# USBready.net
KiCad netlist of a schematic drawn in EAGLE
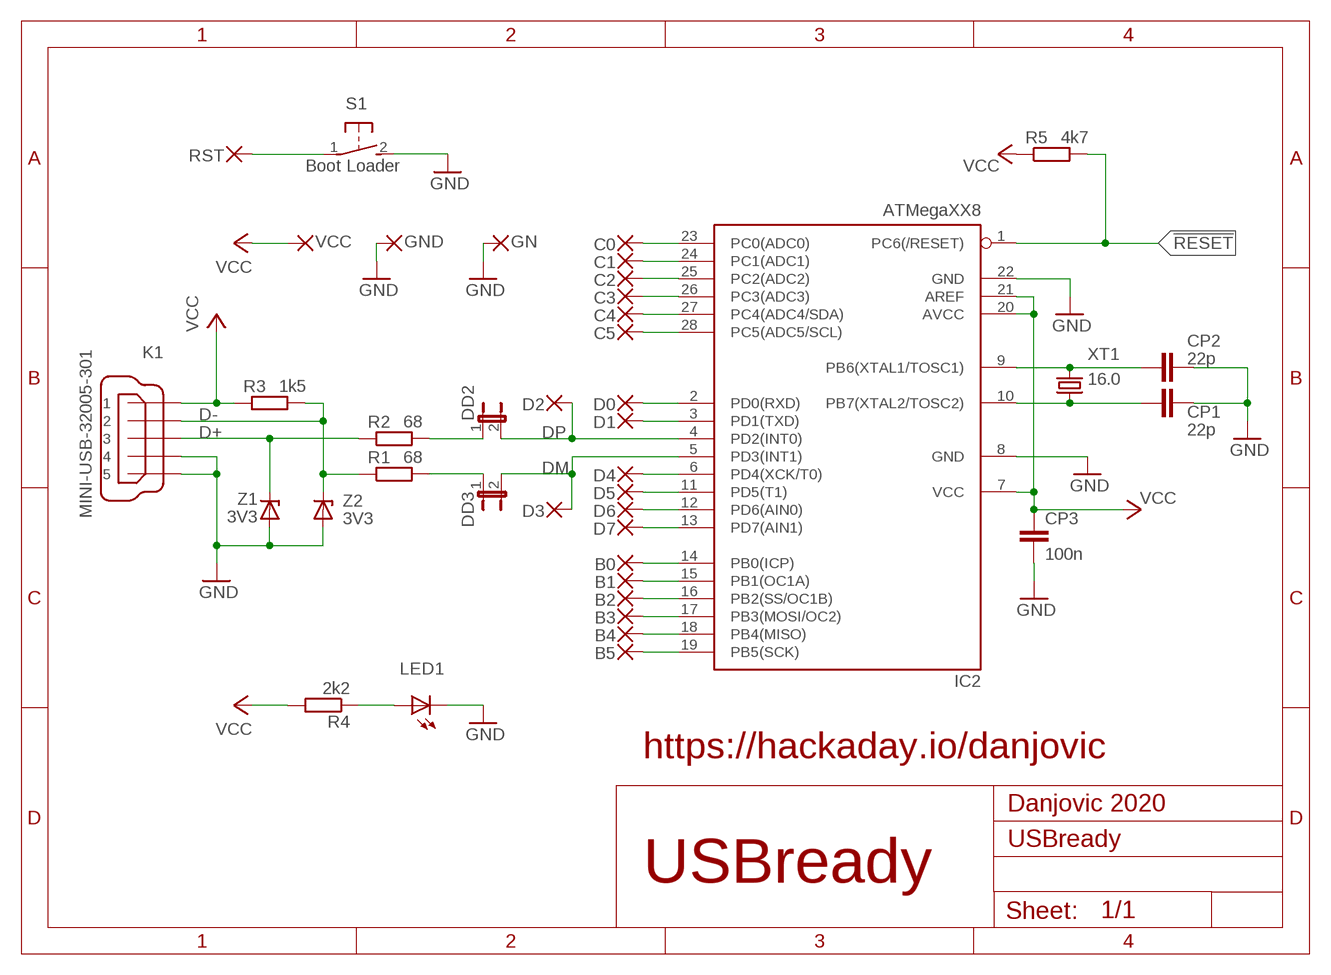
[diagram p0: schematic, sheet 1]

(export (version "E")
  (design (tool "Eeschema 10.0.6"))
  (components
    (comp (ref "B0")
      (value "WIREPAD1,6/0,9")
      (footprint "eagle-import:1,6_0,9")
      (libsource (lib "eagle-import") (part "WIREPAD1,6/0,9"))
    )
    (comp (ref "B1")
      (value "WIREPAD1,6/0,9")
      (footprint "eagle-import:1,6_0,9")
      (libsource (lib "eagle-import") (part "WIREPAD1,6/0,9"))
    )
    (comp (ref "B2")
      (value "WIREPAD1,6/0,9")
      (footprint "eagle-import:1,6_0,9")
      (libsource (lib "eagle-import") (part "WIREPAD1,6/0,9"))
    )
    (comp (ref "B3")
      (value "WIREPAD1,6/0,9")
      (footprint "eagle-import:1,6_0,9")
      (libsource (lib "eagle-import") (part "WIREPAD1,6/0,9"))
    )
    (comp (ref "B4")
      (value "WIREPAD1,6/0,9")
      (footprint "eagle-import:1,6_0,9")
      (libsource (lib "eagle-import") (part "WIREPAD1,6/0,9"))
    )
    (comp (ref "B5")
      (value "WIREPAD1,6/0,9")
      (footprint "eagle-import:1,6_0,9")
      (libsource (lib "eagle-import") (part "WIREPAD1,6/0,9"))
    )
    (comp (ref "C0")
      (value "WIREPAD1,6/0,9")
      (footprint "eagle-import:1,6_0,9")
      (libsource (lib "eagle-import") (part "WIREPAD1,6/0,9"))
    )
    (comp (ref "C1")
      (value "WIREPAD1,6/0,9")
      (footprint "eagle-import:1,6_0,9")
      (libsource (lib "eagle-import") (part "WIREPAD1,6/0,9"))
    )
    (comp (ref "C2")
      (value "WIREPAD1,6/0,9")
      (footprint "eagle-import:1,6_0,9")
      (libsource (lib "eagle-import") (part "WIREPAD1,6/0,9"))
    )
    (comp (ref "C3")
      (value "WIREPAD1,6/0,9")
      (footprint "eagle-import:1,6_0,9")
      (libsource (lib "eagle-import") (part "WIREPAD1,6/0,9"))
    )
    (comp (ref "C4")
      (value "WIREPAD1,6/0,9")
      (footprint "eagle-import:1,6_0,9")
      (libsource (lib "eagle-import") (part "WIREPAD1,6/0,9"))
    )
    (comp (ref "C5")
      (value "WIREPAD1,6/0,9")
      (footprint "eagle-import:1,6_0,9")
      (libsource (lib "eagle-import") (part "WIREPAD1,6/0,9"))
    )
    (comp (ref "CP1")
      (value "22p")
      (footprint "eagle-import:C0805")
      (libsource (lib "eagle-import") (part "C-EUC0805"))
    )
    (comp (ref "CP2")
      (value "22p")
      (footprint "eagle-import:C0805")
      (libsource (lib "eagle-import") (part "C-EUC0805"))
    )
    (comp (ref "CP3")
      (value "100n")
      (footprint "eagle-import:C0805")
      (libsource (lib "eagle-import") (part "C-EUC0805"))
    )
    (comp (ref "D0")
      (value "WIREPAD1,6/0,9")
      (footprint "eagle-import:1,6_0,9")
      (libsource (lib "eagle-import") (part "WIREPAD1,6/0,9"))
    )
    (comp (ref "D1")
      (value "WIREPAD1,6/0,9")
      (footprint "eagle-import:1,6_0,9")
      (libsource (lib "eagle-import") (part "WIREPAD1,6/0,9"))
    )
    (comp (ref "D2")
      (value "WIREPAD1,6/0,9")
      (footprint "eagle-import:1,6_0,9")
      (libsource (lib "eagle-import") (part "WIREPAD1,6/0,9"))
    )
    (comp (ref "D3")
      (value "WIREPAD1,6/0,9")
      (footprint "eagle-import:1,6_0,9")
      (libsource (lib "eagle-import") (part "WIREPAD1,6/0,9"))
    )
    (comp (ref "D4")
      (value "WIREPAD1,6/0,9")
      (footprint "eagle-import:1,6_0,9")
      (libsource (lib "eagle-import") (part "WIREPAD1,6/0,9"))
    )
    (comp (ref "D5")
      (value "WIREPAD1,6/0,9")
      (footprint "eagle-import:1,6_0,9")
      (libsource (lib "eagle-import") (part "WIREPAD1,6/0,9"))
    )
    (comp (ref "D6")
      (value "WIREPAD1,6/0,9")
      (footprint "eagle-import:1,6_0,9")
      (libsource (lib "eagle-import") (part "WIREPAD1,6/0,9"))
    )
    (comp (ref "D7")
      (value "WIREPAD1,6/0,9")
      (footprint "eagle-import:1,6_0,9")
      (libsource (lib "eagle-import") (part "WIREPAD1,6/0,9"))
    )
    (comp (ref "DD2")
      (value "JP1E")
      (footprint "eagle-import:JP1")
      (libsource (lib "eagle-import") (part "JP1E"))
    )
    (comp (ref "DD3")
      (value "JP1E")
      (footprint "eagle-import:JP1")
      (libsource (lib "eagle-import") (part "JP1E"))
    )
    (comp (ref "GN")
      (value "WIREPAD1,6/0,9")
      (footprint "eagle-import:1,6_0,9")
      (libsource (lib "eagle-import") (part "WIREPAD1,6/0,9"))
    )
    (comp (ref "GND")
      (value "WIREPAD1,6/0,9")
      (footprint "eagle-import:1,6_0,9")
      (libsource (lib "eagle-import") (part "WIREPAD1,6/0,9"))
    )
    (comp (ref "IC2")
      (value "ATMegaXX8")
      (footprint "eagle-import:DIL28-3")
      (libsource (lib "eagle-import") (part "MEGA8-P"))
    )
    (comp (ref "K1")
      (value "MINI-USB-32005-301")
      (footprint "eagle-import:32005-301")
      (libsource (lib "eagle-import") (part "MINI-USB-32005-301"))
    )
    (comp (ref "LED1")
      (value "LEDSML1206")
      (footprint "eagle-import:SML1206")
      (libsource (lib "eagle-import") (part "LEDSML1206"))
    )
    (comp (ref "R1")
      (value "68")
      (footprint "eagle-import:M0805")
      (libsource (lib "eagle-import") (part "R-EU_M0805"))
    )
    (comp (ref "R2")
      (value "68")
      (footprint "eagle-import:M0805")
      (libsource (lib "eagle-import") (part "R-EU_M0805"))
    )
    (comp (ref "R3")
      (value "1k5")
      (footprint "eagle-import:R0805")
      (libsource (lib "eagle-import") (part "R-EU_R0805"))
    )
    (comp (ref "R4")
      (value "2k2")
      (footprint "eagle-import:R0805")
      (libsource (lib "eagle-import") (part "R-EU_R0805"))
    )
    (comp (ref "R5")
      (value "4k7")
      (footprint "eagle-import:M0805")
      (libsource (lib "eagle-import") (part "R-EU_M0805"))
    )
    (comp (ref "RST")
      (value "WIREPAD1,6/0,9")
      (footprint "eagle-import:1,6_0,9")
      (libsource (lib "eagle-import") (part "WIREPAD1,6/0,9"))
    )
    (comp (ref "S1")
      (value "31-XX")
      (footprint "eagle-import:B3F-31XX")
      (fields (field (name "MPN") "B3F-3100"))
      (libsource (lib "eagle-import") (part "31-XX"))
    )
    (comp (ref "VCC")
      (value "WIREPAD1,6/0,9")
      (footprint "eagle-import:1,6_0,9")
      (libsource (lib "eagle-import") (part "WIREPAD1,6/0,9"))
    )
    (comp (ref "XT1")
      (value "16.0")
      (footprint "eagle-import:HC49_S")
      (libsource (lib "eagle-import") (part "CRYSTALHC49S"))
    )
    (comp (ref "Z1")
      (value "3V3")
      (footprint "eagle-import:SOD80C")
      (libsource (lib "eagle-import") (part "ZENER-DIODESOD80C"))
    )
    (comp (ref "Z2")
      (value "3V3")
      (footprint "eagle-import:SOD80C")
      (libsource (lib "eagle-import") (part "ZENER-DIODESOD80C"))
    )
  )
  (nets
    (net (code "1") (name "/D+") (class "Default")
      (node (ref "K1") (pin "3") (pinfunction "3_3") (pintype "passive"))
      (node (ref "R2") (pin "1") (pinfunction "1_1") (pintype "passive"))
      (node (ref "Z1") (pin "C") (pinfunction "C_C") (pintype "passive"))
    )
    (net (code "2") (name "/D-") (class "Default")
      (node (ref "K1") (pin "2") (pinfunction "2_2") (pintype "passive"))
      (node (ref "R1") (pin "1") (pinfunction "1_1") (pintype "passive"))
      (node (ref "R3") (pin "2") (pinfunction "2_2") (pintype "passive"))
      (node (ref "Z2") (pin "C") (pinfunction "C_C") (pintype "passive"))
    )
    (net (code "3") (name "/DM") (class "Default")
      (node (ref "D3") (pin "1") (pinfunction "P_1") (pintype "passive"))
      (node (ref "DD3") (pin "2") (pinfunction "2_2") (pintype "passive"))
      (node (ref "IC2") (pin "5") (pinfunction "PD3(INT1)_5") (pintype "bidirectional"))
    )
    (net (code "4") (name "/DP") (class "Default")
      (node (ref "D2") (pin "1") (pinfunction "P_1") (pintype "passive"))
      (node (ref "DD2") (pin "2") (pinfunction "2_2") (pintype "passive"))
      (node (ref "IC2") (pin "4") (pinfunction "PD2(INT0)_4") (pintype "bidirectional"))
    )
    (net (code "5") (name "/~{RESET}") (class "Default")
      (node (ref "IC2") (pin "1") (pinfunction "PC6(/RESET)_1") (pintype "bidirectional"))
      (node (ref "R5") (pin "2") (pinfunction "2_2") (pintype "passive"))
      (node (ref "RST") (pin "1") (pinfunction "P_1") (pintype "passive"))
      (node (ref "S1") (pin "1") (pinfunction "P_1") (pintype "passive"))
    )
    (net (code "6") (name "GND") (class "Default")
      (node (ref "CP1") (pin "2") (pinfunction "2_2") (pintype "passive"))
      (node (ref "CP2") (pin "2") (pinfunction "2_2") (pintype "passive"))
      (node (ref "CP3") (pin "2") (pinfunction "2_2") (pintype "passive"))
      (node (ref "GN") (pin "1") (pinfunction "P_1") (pintype "passive"))
      (node (ref "GND") (pin "1") (pinfunction "P_1") (pintype "passive"))
      (node (ref "IC2") (pin "22") (pinfunction "GND_22") (pintype "power_in"))
      (node (ref "IC2") (pin "8") (pinfunction "GND_8") (pintype "power_in"))
      (node (ref "K1") (pin "4") (pinfunction "4_4") (pintype "passive"))
      (node (ref "K1") (pin "5") (pinfunction "5_5") (pintype "passive"))
      (node (ref "LED1") (pin "C") (pinfunction "C_C") (pintype "passive"))
      (node (ref "S1") (pin "2") (pinfunction "S_2") (pintype "passive"))
      (node (ref "Z1") (pin "A") (pinfunction "A_A") (pintype "passive"))
      (node (ref "Z2") (pin "A") (pinfunction "A_A") (pintype "passive"))
    )
    (net (code "7") (name "Net-(B0-P)") (class "Default")
      (node (ref "B0") (pin "1") (pinfunction "P_1") (pintype "passive"))
      (node (ref "IC2") (pin "14") (pinfunction "PB0(ICP)_14") (pintype "bidirectional"))
    )
    (net (code "8") (name "Net-(B1-P)") (class "Default")
      (node (ref "B1") (pin "1") (pinfunction "P_1") (pintype "passive"))
      (node (ref "IC2") (pin "15") (pinfunction "PB1(OC1A)_15") (pintype "bidirectional"))
    )
    (net (code "9") (name "Net-(B2-P)") (class "Default")
      (node (ref "B2") (pin "1") (pinfunction "P_1") (pintype "passive"))
      (node (ref "IC2") (pin "16") (pinfunction "PB2(SS/OC1B)_16") (pintype "bidirectional"))
    )
    (net (code "10") (name "Net-(B3-P)") (class "Default")
      (node (ref "B3") (pin "1") (pinfunction "P_1") (pintype "passive"))
      (node (ref "IC2") (pin "17") (pinfunction "PB3(MOSI/OC2)_17") (pintype "bidirectional"))
    )
    (net (code "11") (name "Net-(B4-P)") (class "Default")
      (node (ref "B4") (pin "1") (pinfunction "P_1") (pintype "passive"))
      (node (ref "IC2") (pin "18") (pinfunction "PB4(MISO)_18") (pintype "bidirectional"))
    )
    (net (code "12") (name "Net-(B5-P)") (class "Default")
      (node (ref "B5") (pin "1") (pinfunction "P_1") (pintype "passive"))
      (node (ref "IC2") (pin "19") (pinfunction "PB5(SCK)_19") (pintype "bidirectional"))
    )
    (net (code "13") (name "Net-(C0-P)") (class "Default")
      (node (ref "C0") (pin "1") (pinfunction "P_1") (pintype "passive"))
      (node (ref "IC2") (pin "23") (pinfunction "PC0(ADC0)_23") (pintype "bidirectional"))
    )
    (net (code "14") (name "Net-(C1-P)") (class "Default")
      (node (ref "C1") (pin "1") (pinfunction "P_1") (pintype "passive"))
      (node (ref "IC2") (pin "24") (pinfunction "PC1(ADC1)_24") (pintype "bidirectional"))
    )
    (net (code "15") (name "Net-(C2-P)") (class "Default")
      (node (ref "C2") (pin "1") (pinfunction "P_1") (pintype "passive"))
      (node (ref "IC2") (pin "25") (pinfunction "PC2(ADC2)_25") (pintype "bidirectional"))
    )
    (net (code "16") (name "Net-(C3-P)") (class "Default")
      (node (ref "C3") (pin "1") (pinfunction "P_1") (pintype "passive"))
      (node (ref "IC2") (pin "26") (pinfunction "PC3(ADC3)_26") (pintype "bidirectional"))
    )
    (net (code "17") (name "Net-(C4-P)") (class "Default")
      (node (ref "C4") (pin "1") (pinfunction "P_1") (pintype "passive"))
      (node (ref "IC2") (pin "27") (pinfunction "PC4(ADC4/SDA)_27") (pintype "bidirectional"))
    )
    (net (code "18") (name "Net-(C5-P)") (class "Default")
      (node (ref "C5") (pin "1") (pinfunction "P_1") (pintype "passive"))
      (node (ref "IC2") (pin "28") (pinfunction "PC5(ADC5/SCL)_28") (pintype "bidirectional"))
    )
    (net (code "19") (name "Net-(D0-P)") (class "Default")
      (node (ref "D0") (pin "1") (pinfunction "P_1") (pintype "passive"))
      (node (ref "IC2") (pin "2") (pinfunction "PD0(RXD)_2") (pintype "bidirectional"))
    )
    (net (code "20") (name "Net-(D1-P)") (class "Default")
      (node (ref "D1") (pin "1") (pinfunction "P_1") (pintype "passive"))
      (node (ref "IC2") (pin "3") (pinfunction "PD1(TXD)_3") (pintype "bidirectional"))
    )
    (net (code "21") (name "Net-(D4-P)") (class "Default")
      (node (ref "D4") (pin "1") (pinfunction "P_1") (pintype "passive"))
      (node (ref "IC2") (pin "6") (pinfunction "PD4(XCK/T0)_6") (pintype "bidirectional"))
    )
    (net (code "22") (name "Net-(D5-P)") (class "Default")
      (node (ref "D5") (pin "1") (pinfunction "P_1") (pintype "passive"))
      (node (ref "IC2") (pin "11") (pinfunction "PD5(T1)_11") (pintype "bidirectional"))
    )
    (net (code "23") (name "Net-(D6-P)") (class "Default")
      (node (ref "D6") (pin "1") (pinfunction "P_1") (pintype "passive"))
      (node (ref "IC2") (pin "12") (pinfunction "PD6(AIN0)_12") (pintype "bidirectional"))
    )
    (net (code "24") (name "Net-(D7-P)") (class "Default")
      (node (ref "D7") (pin "1") (pinfunction "P_1") (pintype "passive"))
      (node (ref "IC2") (pin "13") (pinfunction "PD7(AIN1)_13") (pintype "bidirectional"))
    )
    (net (code "25") (name "Net-(DD2-Pad1)") (class "Default")
      (node (ref "DD2") (pin "1") (pinfunction "1_1") (pintype "passive"))
      (node (ref "R2") (pin "2") (pinfunction "2_2") (pintype "passive"))
    )
    (net (code "26") (name "Net-(DD3-Pad1)") (class "Default")
      (node (ref "DD3") (pin "1") (pinfunction "1_1") (pintype "passive"))
      (node (ref "R1") (pin "2") (pinfunction "2_2") (pintype "passive"))
    )
    (net (code "27") (name "Net-(IC2-PB6(XTAL1{slash}TOSC1))") (class "Default")
      (node (ref "CP2") (pin "1") (pinfunction "1_1") (pintype "passive"))
      (node (ref "IC2") (pin "9") (pinfunction "PB6(XTAL1/TOSC1)_9") (pintype "bidirectional"))
      (node (ref "XT1") (pin "2") (pinfunction "2_2") (pintype "passive"))
    )
    (net (code "28") (name "Net-(IC2-PB7(XTAL2{slash}TOSC2))") (class "Default")
      (node (ref "CP1") (pin "1") (pinfunction "1_1") (pintype "passive"))
      (node (ref "IC2") (pin "10") (pinfunction "PB7(XTAL2/TOSC2)_10") (pintype "bidirectional"))
      (node (ref "XT1") (pin "1") (pinfunction "1_1") (pintype "passive"))
    )
    (net (code "29") (name "Net-(LED1-PadA)") (class "Default")
      (node (ref "LED1") (pin "A") (pinfunction "A_A") (pintype "passive"))
      (node (ref "R4") (pin "1") (pinfunction "1_1") (pintype "passive"))
    )
    (net (code "30") (name "VCC") (class "Default")
      (node (ref "CP3") (pin "1") (pinfunction "1_1") (pintype "passive"))
      (node (ref "IC2") (pin "20") (pinfunction "AVCC_20") (pintype "power_in"))
      (node (ref "IC2") (pin "21") (pinfunction "AREF_21") (pintype "passive"))
      (node (ref "IC2") (pin "7") (pinfunction "VCC_7") (pintype "power_in"))
      (node (ref "K1") (pin "1") (pinfunction "1_1") (pintype "passive"))
      (node (ref "R3") (pin "1") (pinfunction "1_1") (pintype "passive"))
      (node (ref "R4") (pin "2") (pinfunction "2_2") (pintype "passive"))
      (node (ref "R5") (pin "1") (pinfunction "1_1") (pintype "passive"))
      (node (ref "VCC") (pin "1") (pinfunction "P_1") (pintype "passive"))
    )
  )
)
